# Top.net
KiCad netlist of a schematic drawn in Altium Designer
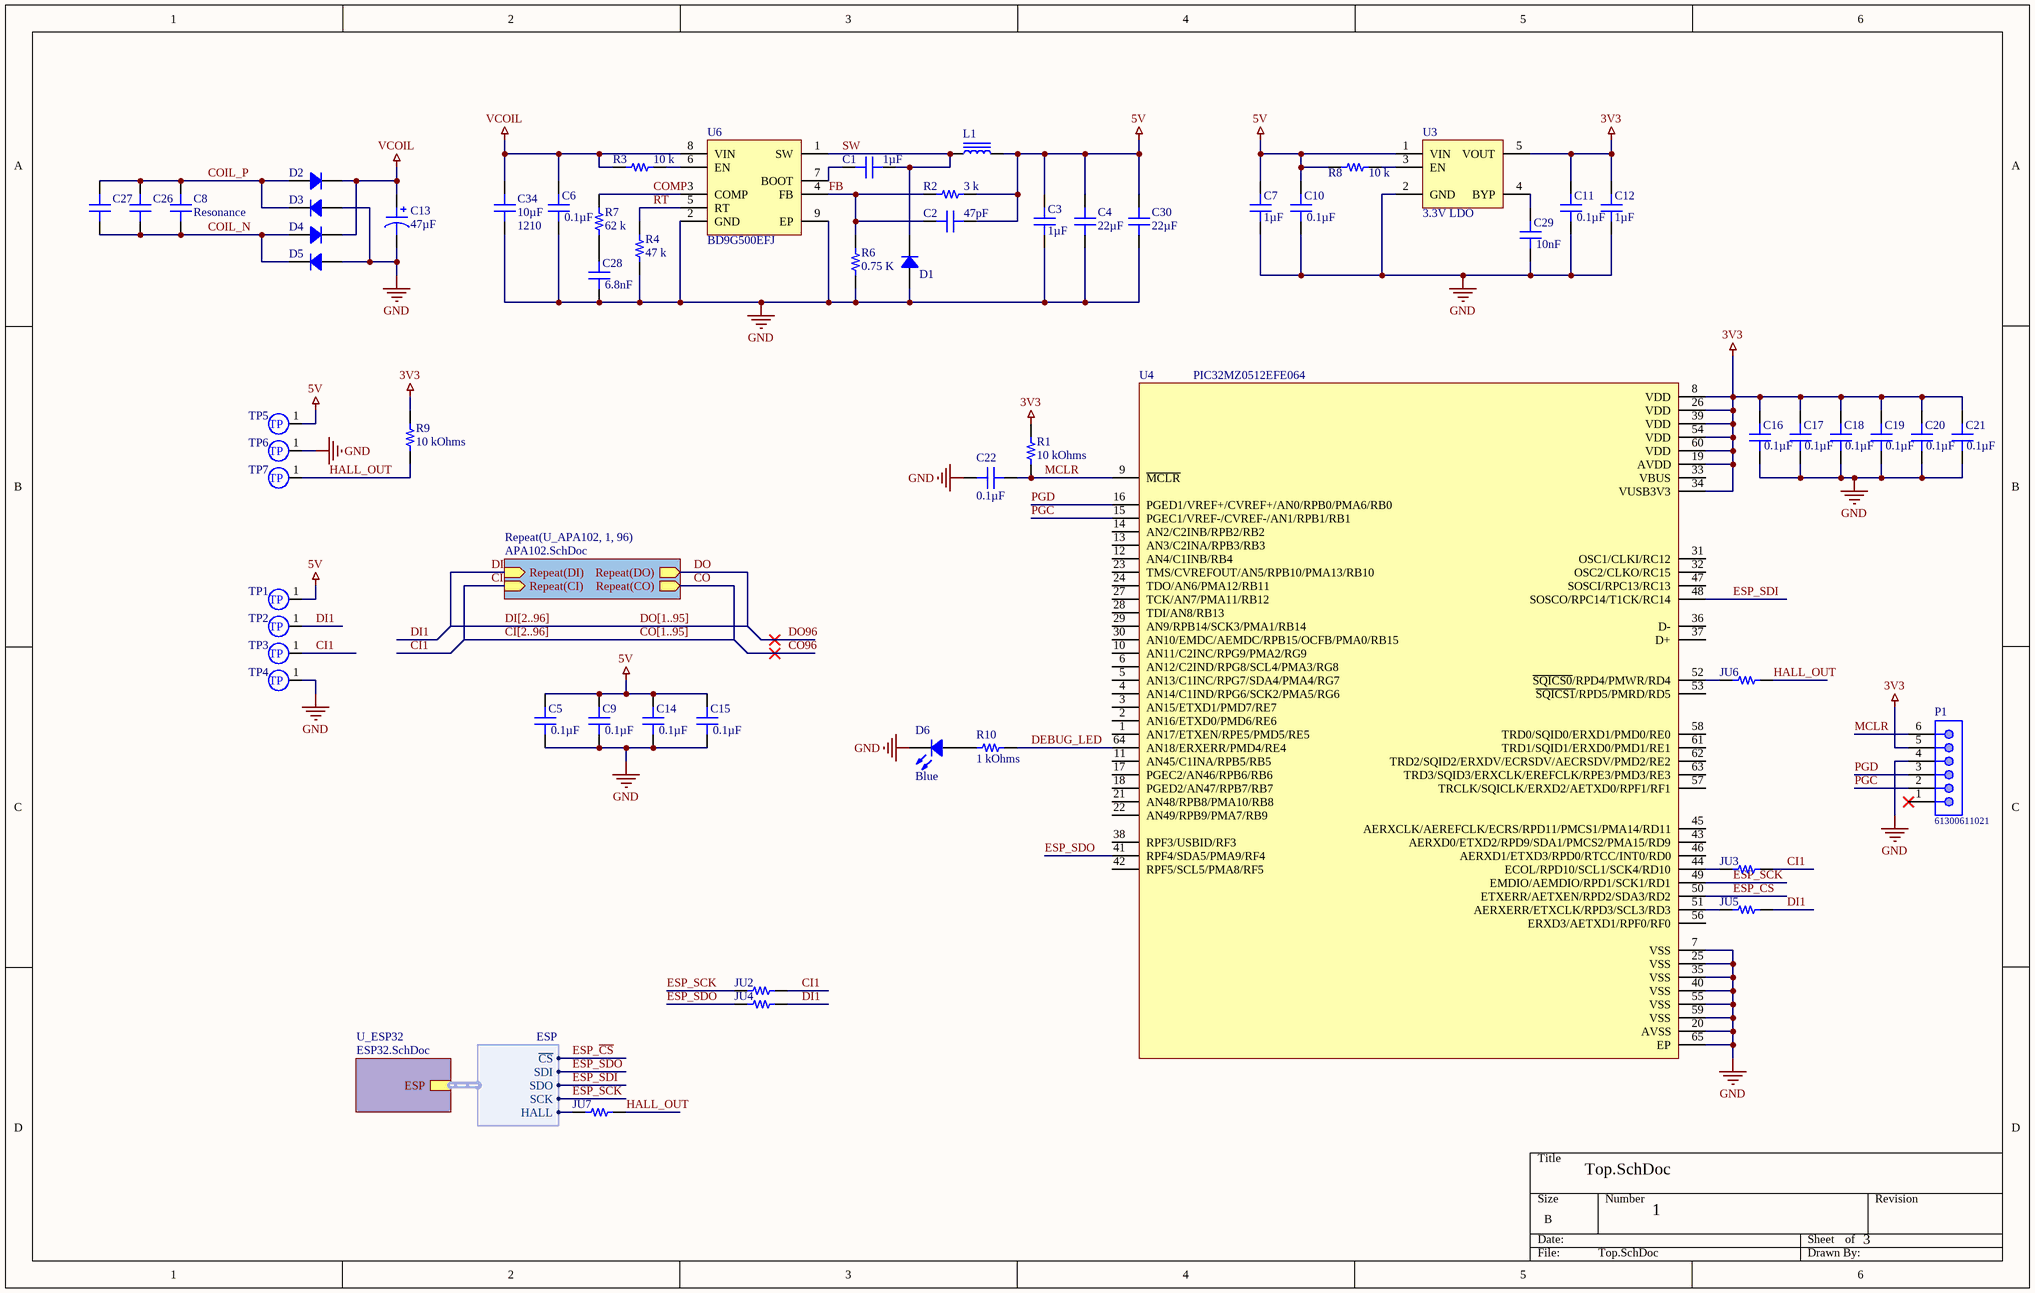
[diagram p0: Top.SchDoc]

(export (version "E")
  (design (tool "Eeschema 10.0.6"))
  (components
    (comp (ref "C1")
      (value "1µF")
      (footprint "CAP 0603_1608")
      (description "CAP CER 1UF 25V X7R 0603")
      (fields
        (field (name "PART NUMBER") "GCJ188R71E105KA01D")
        (field (name "MANUFACTURER") "Murata Electronics")
      )
      (libsource (lib "Celestial Altium Library - altium_library") (part "Capacitor"))
    )
    (comp (ref "C2")
      (value "47pF")
      (footprint "CAP 0603_1608")
      (description "CAP CER 47PF 100V NP0 0603")
      (fields
        (field (name "PART NUMBER") "C1608NP02A470J080AA")
        (field (name "MANUFACTURER") "TDK Corporation")
      )
      (libsource (lib "Celestial Altium Library - altium_library") (part "Capacitor"))
    )
    (comp (ref "C3")
      (value "1µF")
      (footprint "CAP 0603_1608")
      (description "CAP CER 1UF 25V X7R 0603")
      (fields
        (field (name "PART NUMBER") "GCJ188R71E105KA01D")
        (field (name "MANUFACTURER") "Murata Electronics")
      )
      (libsource (lib "Celestial Altium Library - altium_library") (part "Capacitor"))
    )
    (comp (ref "C4")
      (value "22µF")
      (footprint "CAP 0805_2012")
      (description "CAP CER 22UF 16V X5R 0805")
      (fields
        (field (name "PART NUMBER") "CL21A226MOQNNNE")
        (field (name "MANUFACTURER") "Samsung Electro-Mechanics")
      )
      (libsource (lib "Celestial Altium Library - altium_library") (part "Capacitor"))
    )
    (comp (ref "C5")
      (value "0.1µF")
      (footprint "CAP 0603_1608")
      (description "CAP CER 0.1UF 100V 0603 EPOXY")
      (fields
        (field (name "PART NUMBER") "GCG188R92A104KA03D")
        (field (name "MANUFACTURER") "Murata Electronics")
      )
      (libsource (lib "Celestial Altium Library - altium_library") (part "Capacitor"))
    )
    (comp (ref "C6")
      (value "0.1µF")
      (footprint "CAP 0603_1608")
      (description "CAP CER 0.1UF 100V 0603 EPOXY")
      (fields
        (field (name "PART NUMBER") "GCG188R92A104KA03D")
        (field (name "MANUFACTURER") "Murata Electronics")
      )
      (libsource (lib "Celestial Altium Library - altium_library") (part "Capacitor"))
    )
    (comp (ref "C7")
      (value "1µF")
      (footprint "CAP 0603_1608")
      (description "CAP CER 1UF 25V X7R 0603")
      (fields
        (field (name "PART NUMBER") "GCJ188R71E105KA01D")
        (field (name "MANUFACTURER") "Murata Electronics")
      )
      (libsource (lib "Celestial Altium Library - altium_library") (part "Capacitor"))
    )
    (comp (ref "C8")
      (value "Resonance")
      (footprint "CAP 1206_3216 - 1.8MM")
      (description "CAP, MLCC, 1206/3216, 100V, X7R,")
      (fields (field (name "PART NUMBER") "HMF316B7103KFHT") (field (name "MANUFACTURER") "Taiyo Yuden"))
      (libsource (lib "Celestial Altium Library - altium_library") (part "Capacitor"))
    )
    (comp (ref "C9")
      (value "0.1µF")
      (footprint "CAP 0603_1608")
      (description "CAP CER 0.1UF 100V 0603 EPOXY")
      (fields
        (field (name "PART NUMBER") "GCG188R92A104KA03D")
        (field (name "MANUFACTURER") "Murata Electronics")
      )
      (libsource (lib "Celestial Altium Library - altium_library") (part "Capacitor"))
    )
    (comp (ref "C10")
      (value "0.1µF")
      (footprint "CAP 0603_1608")
      (description "CAP CER 0.1UF 100V 0603 EPOXY")
      (fields
        (field (name "PART NUMBER") "GCG188R92A104KA03D")
        (field (name "MANUFACTURER") "Murata Electronics")
      )
      (libsource (lib "Celestial Altium Library - altium_library") (part "Capacitor"))
    )
    (comp (ref "C11")
      (value "0.1µF")
      (footprint "CAP 0603_1608")
      (description "CAP CER 0.1UF 100V 0603 EPOXY")
      (fields
        (field (name "PART NUMBER") "GCG188R92A104KA03D")
        (field (name "MANUFACTURER") "Murata Electronics")
      )
      (libsource (lib "Celestial Altium Library - altium_library") (part "Capacitor"))
    )
    (comp (ref "C12")
      (value "1µF")
      (footprint "CAP 0603_1608")
      (description "CAP CER 1UF 25V X7R 0603")
      (fields
        (field (name "PART NUMBER") "GCJ188R71E105KA01D")
        (field (name "MANUFACTURER") "Murata Electronics")
      )
      (libsource (lib "Celestial Altium Library - altium_library") (part "Capacitor"))
    )
    (comp (ref "C13")
      (value "47µF")
      (footprint "CAP ALSMD 6.6MM H6.1MM")
      (description "ALUMINUM CAPACITOR")
      (fields
        (field (name "PART NUMBER") "EMHL160ARA470MF61G")
        (field (name "MANUFACTURER") "United Chemi-Con")
      )
      (libsource (lib "Celestial Altium Library - altium_library") (part "Polarised Capacitor"))
    )
    (comp (ref "C14")
      (value "0.1µF")
      (footprint "CAP 0603_1608")
      (description "CAP CER 0.1UF 100V 0603 EPOXY")
      (fields
        (field (name "PART NUMBER") "GCG188R92A104KA03D")
        (field (name "MANUFACTURER") "Murata Electronics")
      )
      (libsource (lib "Celestial Altium Library - altium_library") (part "Capacitor"))
    )
    (comp (ref "C15")
      (value "0.1µF")
      (footprint "CAP 0603_1608")
      (description "CAP CER 0.1UF 100V 0603 EPOXY")
      (fields
        (field (name "PART NUMBER") "GCG188R92A104KA03D")
        (field (name "MANUFACTURER") "Murata Electronics")
      )
      (libsource (lib "Celestial Altium Library - altium_library") (part "Capacitor"))
    )
    (comp (ref "C16")
      (value "0.1µF")
      (footprint "CAP 0603_1608")
      (description "CAP CER 0.1UF 100V 0603 EPOXY")
      (fields
        (field (name "PART NUMBER") "GCG188R92A104KA03D")
        (field (name "MANUFACTURER") "Murata Electronics")
      )
      (libsource (lib "Celestial Altium Library - altium_library") (part "Capacitor"))
    )
    (comp (ref "C17")
      (value "0.1µF")
      (footprint "CAP 0603_1608")
      (description "CAP CER 0.1UF 100V 0603 EPOXY")
      (fields
        (field (name "PART NUMBER") "GCG188R92A104KA03D")
        (field (name "MANUFACTURER") "Murata Electronics")
      )
      (libsource (lib "Celestial Altium Library - altium_library") (part "Capacitor"))
    )
    (comp (ref "C18")
      (value "0.1µF")
      (footprint "CAP 0603_1608")
      (description "CAP CER 0.1UF 100V 0603 EPOXY")
      (fields
        (field (name "PART NUMBER") "GCG188R92A104KA03D")
        (field (name "MANUFACTURER") "Murata Electronics")
      )
      (libsource (lib "Celestial Altium Library - altium_library") (part "Capacitor"))
    )
    (comp (ref "C19")
      (value "0.1µF")
      (footprint "CAP 0603_1608")
      (description "CAP CER 0.1UF 100V 0603 EPOXY")
      (fields
        (field (name "PART NUMBER") "GCG188R92A104KA03D")
        (field (name "MANUFACTURER") "Murata Electronics")
      )
      (libsource (lib "Celestial Altium Library - altium_library") (part "Capacitor"))
    )
    (comp (ref "C20")
      (value "0.1µF")
      (footprint "CAP 0603_1608")
      (description "CAP CER 0.1UF 100V 0603 EPOXY")
      (fields
        (field (name "PART NUMBER") "GCG188R92A104KA03D")
        (field (name "MANUFACTURER") "Murata Electronics")
      )
      (libsource (lib "Celestial Altium Library - altium_library") (part "Capacitor"))
    )
    (comp (ref "C21")
      (value "0.1µF")
      (footprint "CAP 0603_1608")
      (description "CAP CER 0.1UF 100V 0603 EPOXY")
      (fields
        (field (name "PART NUMBER") "GCG188R92A104KA03D")
        (field (name "MANUFACTURER") "Murata Electronics")
      )
      (libsource (lib "Celestial Altium Library - altium_library") (part "Capacitor"))
    )
    (comp (ref "C22")
      (value "0.1µF")
      (footprint "CAP 0603_1608")
      (description "CAP CER 0.1UF 100V 0603 EPOXY")
      (fields
        (field (name "PART NUMBER") "GCG188R92A104KA03D")
        (field (name "MANUFACTURER") "Murata Electronics")
      )
      (libsource (lib "Celestial Altium Library - altium_library") (part "Capacitor"))
    )
    (comp (ref "C26")
      (value "Resonance")
      (footprint "CAP 1206_3216 - 1.8MM")
      (description "CAP, MLCC, 1206/3216, 100V, X7R,")
      (fields (field (name "PART NUMBER") "HMF316B7103KFHT") (field (name "MANUFACTURER") "Taiyo Yuden"))
      (libsource (lib "Celestial Altium Library - altium_library") (part "Capacitor"))
    )
    (comp (ref "C27")
      (value "Resonance")
      (footprint "CAP 1206_3216 - 1.8MM")
      (description "CAP, MLCC, 1206/3216, 100V, X7R,")
      (fields (field (name "PART NUMBER") "HMF316B7103KFHT") (field (name "MANUFACTURER") "Taiyo Yuden"))
      (libsource (lib "Celestial Altium Library - altium_library") (part "Capacitor"))
    )
    (comp (ref "C28")
      (value "6.8nF")
      (footprint "CAP 0603_1608")
      (description "CAP CER 0.1UF 100V 0603 EPOXY")
      (fields
        (field (name "PART NUMBER") "GCG188R92A104KA03D")
        (field (name "MANUFACTURER") "Murata Electronics")
      )
      (libsource (lib "Celestial Altium Library - altium_library") (part "Capacitor"))
    )
    (comp (ref "C29")
      (value "10nF")
      (footprint "CAP 0603_1608")
      (description "CAP CER 0.1UF 100V 0603 EPOXY")
      (fields
        (field (name "PART NUMBER") "GCG188R92A104KA03D")
        (field (name "MANUFACTURER") "Murata Electronics")
      )
      (libsource (lib "Celestial Altium Library - altium_library") (part "Capacitor"))
    )
    (comp (ref "C30")
      (value "22µF")
      (footprint "CAP 0805_2012")
      (description "CAP CER 22UF 16V X5R 0805")
      (fields
        (field (name "PART NUMBER") "CL21A226MOQNNNE")
        (field (name "MANUFACTURER") "Samsung Electro-Mechanics")
      )
      (libsource (lib "Celestial Altium Library - altium_library") (part "Capacitor"))
    )
    (comp (ref "C34")
      (value "10µF")
      (footprint "CAP 1210_3225 - 2.8MM")
      (description "CAP CER 100UF 16V X5R 1210")
      (fields
        (field (name "PART NUMBER") "EMK325ABJ107MM-P")
        (field (name "DEVICE PACKAGE") "1210")
        (field (name "MANUFACTURER") "Taiyo Yuden")
      )
      (libsource (lib "Celestial Altium Library - altium_library") (part "Capacitor"))
    )
    (comp (ref "D1")
      (value "STPS340UY")
      (footprint "DO214AA SMB")
      (description "DIODE SCHOTTKY 40V 3A SMB")
      (fields (field (name "MANUFACTURER") "STMicroelectronics"))
      (libsource (lib "Celestial Altium Library - altium_library") (part "Diode"))
    )
    (comp (ref "D2")
      (value "STPS340UY")
      (footprint "DO214AA SMB")
      (description "DIODE SCHOTTKY 40V 3A SMB")
      (fields (field (name "MANUFACTURER") "STMicroelectronics"))
      (libsource (lib "Celestial Altium Library - altium_library") (part "Diode"))
    )
    (comp (ref "D3")
      (value "STPS340UY")
      (footprint "DO214AA SMB")
      (description "DIODE SCHOTTKY 40V 3A SMB")
      (fields (field (name "MANUFACTURER") "STMicroelectronics"))
      (libsource (lib "Celestial Altium Library - altium_library") (part "Diode"))
    )
    (comp (ref "D4")
      (value "STPS340UY")
      (footprint "DO214AA SMB")
      (description "DIODE SCHOTTKY 40V 3A SMB")
      (fields (field (name "MANUFACTURER") "STMicroelectronics"))
      (libsource (lib "Celestial Altium Library - altium_library") (part "Diode"))
    )
    (comp (ref "D5")
      (value "STPS340UY")
      (footprint "DO214AA SMB")
      (description "DIODE SCHOTTKY 40V 3A SMB")
      (fields (field (name "MANUFACTURER") "STMicroelectronics"))
      (libsource (lib "Celestial Altium Library - altium_library") (part "Diode"))
    )
    (comp (ref "D6")
      (value "Blue")
      (footprint "LED 0603_1608 GREEN")
      (description "Blue LED")
      (fields (field (name "PART NUMBER") "XZCDGK53W-8VF") (field (name "MANUFACTURER") "SunLED"))
      (libsource (lib "Celestial Altium Library - altium_library") (part "LED"))
    )
    (comp (ref "JU2")
      (value "~")
      (footprint "RES 0805_2012")
      (description "Jumper")
      (fields
        (field (name "PART NUMBER") "TLRZ2ATTD")
        (field (name "MANUFACTURER") "KOA Speer Electronics, Inc.")
      )
      (libsource (lib "Celestial Altium Library - altium_library") (part "Resistor"))
    )
    (comp (ref "JU3")
      (value "~")
      (footprint "RES 0805_2012")
      (description "Jumper")
      (fields
        (field (name "PART NUMBER") "TLRZ2ATTD")
        (field (name "MANUFACTURER") "KOA Speer Electronics, Inc.")
      )
      (libsource (lib "Celestial Altium Library - altium_library") (part "Resistor"))
    )
    (comp (ref "JU4")
      (value "~")
      (footprint "RES 0805_2012")
      (description "Jumper")
      (fields
        (field (name "PART NUMBER") "TLRZ2ATTD")
        (field (name "MANUFACTURER") "KOA Speer Electronics, Inc.")
      )
      (libsource (lib "Celestial Altium Library - altium_library") (part "Resistor"))
    )
    (comp (ref "JU5")
      (value "~")
      (footprint "RES 0805_2012")
      (description "Jumper")
      (fields
        (field (name "PART NUMBER") "TLRZ2ATTD")
        (field (name "MANUFACTURER") "KOA Speer Electronics, Inc.")
      )
      (libsource (lib "Celestial Altium Library - altium_library") (part "Resistor"))
    )
    (comp (ref "JU6")
      (value "~")
      (footprint "RES 0805_2012")
      (description "Jumper")
      (fields
        (field (name "PART NUMBER") "TLRZ2ATTD")
        (field (name "MANUFACTURER") "KOA Speer Electronics, Inc.")
      )
      (libsource (lib "Celestial Altium Library - altium_library") (part "Resistor"))
    )
    (comp (ref "JU7")
      (value "~")
      (footprint "RES 0805_2012")
      (description "Jumper")
      (fields
        (field (name "PART NUMBER") "TLRZ2ATTD")
        (field (name "MANUFACTURER") "KOA Speer Electronics, Inc.")
      )
      (libsource (lib "Celestial Altium Library - altium_library") (part "Resistor"))
    )
    (comp (ref "L1")
      (value "MPL-AL5050-5R6")
      (footprint "MPL-AL5050-5R6")
      (description "FIXED IND 5.6UH 6.8A 20 MOHM SMD")
      (fields (field (name "MF") "Laird-Signal Integrity Products") (field (name "MP") "MGV05021R0M-10"))
      (libsource (lib "IC") (part "MPL-AL5050-5R6"))
    )
    (comp (ref "P1")
      (value "61300611021")
      (footprint "61300611021")
      (description "WR-PHD Pin Header, THT, pitch 2.54mm, Single Row, Angled, 6p")
      (fields (field (name "MANUFACTURER") "Wurth Elektronik"))
      (libsource (lib "IC") (part "6pin right angle header - no holes"))
    )
    (comp (ref "R1")
      (value "10 kOhms")
      (footprint "RES 0603_1608")
      (description "RES 10K OHM 0.1% 1/16W 0603")
      (fields
        (field (name "PART NUMBER") "RNCS0603BKE10K0")
        (field (name "MANUFACTURER") "Stackpole Electronics Inc")
      )
      (libsource (lib "Celestial Altium Library - altium_library") (part "Resistor"))
    )
    (comp (ref "R2")
      (value "3 k")
      (footprint "RES 0603_1608")
      (description "RES SMD 40.2KOHM 0.5% 1/10W 0603")
      (fields (field (name "PART NUMBER") "RT0603DRD0740K2L") (field (name "MANUFACTURER") "Yageo"))
      (libsource (lib "Celestial Altium Library - altium_library") (part "Resistor"))
    )
    (comp (ref "R3")
      (value "10 k")
      (footprint "RES 0603_1608")
      (description "RES 10K OHM 0.1% 1/16W 0603")
      (fields
        (field (name "PART NUMBER") "RNCS0603BKE10K0")
        (field (name "MANUFACTURER") "Stackpole Electronics Inc")
      )
      (libsource (lib "Celestial Altium Library - altium_library") (part "Resistor"))
    )
    (comp (ref "R4")
      (value "47 k")
      (footprint "RES 0603_1608")
      (description "RES 10K OHM 0.1% 1/16W 0603")
      (fields
        (field (name "PART NUMBER") "RNCS0603BKE10K0")
        (field (name "MANUFACTURER") "Stackpole Electronics Inc")
      )
      (libsource (lib "Celestial Altium Library - altium_library") (part "Resistor"))
    )
    (comp (ref "R6")
      (value "0.75 K")
      (footprint "RES 0603_1608")
      (description "RES 7.68K OHM 1% 1/10W 0603")
      (fields
        (field (name "PART NUMBER") "RMCF0603FT7K68")
        (field (name "MANUFACTURER") "Stackpole Electronics Inc")
      )
      (libsource (lib "Celestial Altium Library - altium_library") (part "Resistor"))
    )
    (comp (ref "R7")
      (value "62 k")
      (footprint "RES 0603_1608")
      (description "RES 10K OHM 0.1% 1/16W 0603")
      (fields
        (field (name "PART NUMBER") "RNCS0603BKE10K0")
        (field (name "MANUFACTURER") "Stackpole Electronics Inc")
      )
      (libsource (lib "Celestial Altium Library - altium_library") (part "Resistor"))
    )
    (comp (ref "R8")
      (value "10 k")
      (footprint "RES 0603_1608")
      (description "RES 10K OHM 0.1% 1/16W 0603")
      (fields
        (field (name "PART NUMBER") "RNCS0603BKE10K0")
        (field (name "MANUFACTURER") "Stackpole Electronics Inc")
      )
      (libsource (lib "Celestial Altium Library - altium_library") (part "Resistor"))
    )
    (comp (ref "R9")
      (value "10 kOhms")
      (footprint "RES 0603_1608")
      (description "RES 10K OHM 0.1% 1/16W 0603")
      (fields
        (field (name "PART NUMBER") "RNCS0603BKE10K0")
        (field (name "MANUFACTURER") "Stackpole Electronics Inc")
      )
      (libsource (lib "Celestial Altium Library - altium_library") (part "Resistor"))
    )
    (comp (ref "R10")
      (value "1 kOhms")
      (footprint "RES 0603_1608")
      (description "RES 1K OHM 0.5% 1/10W 0603")
      (fields
        (field (name "PART NUMBER") "RNCF0603DTE1K00")
        (field (name "MANUFACTURER") "Stackpole Electronics Inc")
      )
      (libsource (lib "Celestial Altium Library - altium_library") (part "Resistor"))
    )
    (comp (ref "TP1")
      (value "TP")
      (footprint "TP")
      (description "Test point")
      (libsource (lib "IC") (part "TP"))
    )
    (comp (ref "TP2")
      (value "TP")
      (footprint "TP")
      (description "Test point")
      (libsource (lib "IC") (part "TP"))
    )
    (comp (ref "TP3")
      (value "TP")
      (footprint "TP")
      (description "Test point")
      (libsource (lib "IC") (part "TP"))
    )
    (comp (ref "TP4")
      (value "TP")
      (footprint "TP")
      (description "Test point")
      (libsource (lib "IC") (part "TP"))
    )
    (comp (ref "TP5")
      (value "TP")
      (footprint "TP")
      (description "Test point")
      (libsource (lib "IC") (part "TP"))
    )
    (comp (ref "TP6")
      (value "TP")
      (footprint "TP")
      (description "Test point")
      (libsource (lib "IC") (part "TP"))
    )
    (comp (ref "TP7")
      (value "TP")
      (footprint "TP")
      (description "Test point")
      (libsource (lib "IC") (part "TP"))
    )
    (comp (ref "U3")
      (value "3.3V LDO")
      (footprint "TI SOT-23-5 DBV")
      (libsource (lib "IC") (part "MIC5504-3.3YM5"))
    )
    (comp (ref "U4")
      (value "PIC32MZ0512EFE064")
      (footprint "QFN50P900X900X100-65N")
      (description "32-bit Microcontrollers - MCU 32-BIT MCU 512KB FL 128KB RAM, No Crypto")
      (fields (field (name "MF") "Microchip") (field (name "MP") "PIC32MZ2048EFG064T-I/PT"))
      (libsource (lib "IC") (part "PIC32MZ0512EFE064-I/PT"))
    )
    (comp (ref "U6")
      (value "BD9G500EFJ")
      (footprint "SOP127P600X100-9N")
      (description "5A Buck")
      (libsource (lib "IC") (part "BD9G500EFJ"))
    )
  )
  (nets
    (net (code "193") (name "/CI1") (class "Default")
      (node (ref "JU2") (pin "1") (pinfunction "1_1") (pintype "passive"))
      (node (ref "JU3") (pin "1") (pinfunction "1_1") (pintype "passive"))
      (node (ref "TP3") (pin "1") (pinfunction "TP_1") (pintype "passive"))
    )
    (net (code "197") (name "/COIL_N") (class "Default")
      (node (ref "C26") (pin "1") (pinfunction "1_1") (pintype "passive"))
      (node (ref "C27") (pin "1") (pinfunction "1_1") (pintype "passive"))
      (node (ref "C8") (pin "1") (pinfunction "1_1") (pintype "passive"))
      (node (ref "D4") (pin "1") (pinfunction "1_1") (pintype "passive"))
      (node (ref "D5") (pin "2") (pinfunction "2_2") (pintype "passive"))
    )
    (net (code "198") (name "/COIL_P") (class "Default")
      (node (ref "C26") (pin "2") (pinfunction "2_2") (pintype "passive"))
      (node (ref "C27") (pin "2") (pinfunction "2_2") (pintype "passive"))
      (node (ref "C8") (pin "2") (pinfunction "2_2") (pintype "passive"))
      (node (ref "D2") (pin "1") (pinfunction "1_1") (pintype "passive"))
      (node (ref "D3") (pin "2") (pinfunction "2_2") (pintype "passive"))
    )
    (net (code "199") (name "/COMP") (class "Default")
      (node (ref "R7") (pin "1") (pinfunction "1_1") (pintype "passive"))
      (node (ref "U6") (pin "3") (pinfunction "COMP_3") (pintype "passive"))
    )
    (net (code "200") (name "/DEBUG_LED") (class "Default")
      (node (ref "R10") (pin "1") (pinfunction "1_1") (pintype "passive"))
      (node (ref "U4") (pin "64") (pinfunction "AN18/ERXERR/PMD4/RE4_64") (pintype "passive"))
    )
    (net (code "202") (name "/DI1") (class "Default")
      (node (ref "JU4") (pin "1") (pinfunction "1_1") (pintype "passive"))
      (node (ref "JU5") (pin "1") (pinfunction "1_1") (pintype "passive"))
      (node (ref "TP2") (pin "1") (pinfunction "TP_1") (pintype "passive"))
    )
    (net (code "206") (name "/ESP_SCK") (class "Default")
      (node (ref "JU2") (pin "2") (pinfunction "2_2") (pintype "passive"))
      (node (ref "U4") (pin "49") (pinfunction "EMDIO/AEMDIO/RPD1/SCK1/RD1_49") (pintype "passive"))
    )
    (net (code "207") (name "/ESP_SDI") (class "Default")
      (node (ref "U4") (pin "48") (pinfunction "SOSCO/RPC14/T1CK/RC14_48") (pintype "passive"))
    )
    (net (code "208") (name "/ESP_SDO") (class "Default")
      (node (ref "JU4") (pin "2") (pinfunction "2_2") (pintype "passive"))
      (node (ref "U4") (pin "41") (pinfunction "RPF4/SDA5/PMA9/RF4_41") (pintype "passive"))
    )
    (net (code "209") (name "/ESP_~{CS}") (class "Default")
      (node (ref "U4") (pin "50") (pinfunction "ETXERR/AETXEN/RPD2/SDA3/RD2_50") (pintype "passive"))
    )
    (net (code "210") (name "/FB") (class "Default")
      (node (ref "C2") (pin "2") (pinfunction "2_2") (pintype "passive"))
      (node (ref "R2") (pin "1") (pinfunction "1_1") (pintype "passive"))
      (node (ref "R6") (pin "2") (pinfunction "2_2") (pintype "passive"))
      (node (ref "U6") (pin "4") (pinfunction "FB_4") (pintype "passive"))
    )
    (net (code "211") (name "/HALL") (class "Default")
      (node (ref "JU7") (pin "2") (pinfunction "2_2") (pintype "passive"))
    )
    (net (code "212") (name "/HALL_OUT") (class "Default")
      (node (ref "JU6") (pin "1") (pinfunction "1_1") (pintype "passive"))
      (node (ref "JU7") (pin "1") (pinfunction "1_1") (pintype "passive"))
      (node (ref "R9") (pin "1") (pinfunction "1_1") (pintype "passive"))
      (node (ref "TP7") (pin "1") (pinfunction "TP_1") (pintype "passive"))
    )
    (net (code "213") (name "/MCLR") (class "Default")
      (node (ref "C22") (pin "1") (pinfunction "1_1") (pintype "passive"))
      (node (ref "P1") (pin "6") (pinfunction "6_6") (pintype "passive"))
      (node (ref "R1") (pin "1") (pinfunction "1_1") (pintype "passive"))
      (node (ref "U4") (pin "9") (pinfunction "~{MCLR}_9") (pintype "passive"))
    )
    (net (code "214") (name "/PGC") (class "Default")
      (node (ref "P1") (pin "2") (pinfunction "2_2") (pintype "passive"))
      (node (ref "U4") (pin "15") (pinfunction "PGEC1/VREF-/CVREF-/AN1/RPB1/RB1_15") (pintype "passive"))
    )
    (net (code "215") (name "/PGD") (class "Default")
      (node (ref "P1") (pin "3") (pinfunction "3_3") (pintype "passive"))
      (node (ref "U4") (pin "16") (pinfunction "PGED1/VREF+/CVREF+/AN0/RPB0/PMA6/RB0_16") (pintype "passive"))
    )
    (net (code "216") (name "/RT") (class "Default")
      (node (ref "R4") (pin "1") (pinfunction "1_1") (pintype "passive"))
      (node (ref "U6") (pin "5") (pinfunction "RT_5") (pintype "passive"))
    )
    (net (code "217") (name "/SW") (class "Default")
      (node (ref "C1") (pin "2") (pinfunction "2_2") (pintype "passive"))
      (node (ref "D1") (pin "2") (pinfunction "2_2") (pintype "passive"))
      (node (ref "L1") (pin "1") (pinfunction "1_1") (pintype "passive"))
      (node (ref "U6") (pin "1") (pinfunction "SW_1") (pintype "passive"))
    )
    (net (code "219") (name "3V3") (class "Default")
      (node (ref "C11") (pin "1") (pinfunction "1_1") (pintype "passive"))
      (node (ref "C12") (pin "2") (pinfunction "2_2") (pintype "passive"))
      (node (ref "C16") (pin "1") (pinfunction "1_1") (pintype "passive"))
      (node (ref "C17") (pin "1") (pinfunction "1_1") (pintype "passive"))
      (node (ref "C18") (pin "1") (pinfunction "1_1") (pintype "passive"))
      (node (ref "C19") (pin "1") (pinfunction "1_1") (pintype "passive"))
      (node (ref "C20") (pin "1") (pinfunction "1_1") (pintype "passive"))
      (node (ref "C21") (pin "1") (pinfunction "1_1") (pintype "passive"))
      (node (ref "P1") (pin "5") (pinfunction "5_5") (pintype "passive"))
      (node (ref "R1") (pin "2") (pinfunction "2_2") (pintype "passive"))
      (node (ref "R9") (pin "2") (pinfunction "2_2") (pintype "passive"))
      (node (ref "U3") (pin "5") (pinfunction "VOUT_5") (pintype "passive"))
      (node (ref "U4") (pin "19") (pinfunction "AVDD_19") (pintype "power_in"))
      (node (ref "U4") (pin "26") (pinfunction "VDD_26") (pintype "power_in"))
      (node (ref "U4") (pin "34") (pinfunction "VUSB3V3_34") (pintype "power_in"))
      (node (ref "U4") (pin "39") (pinfunction "VDD_39") (pintype "power_in"))
      (node (ref "U4") (pin "54") (pinfunction "VDD_54") (pintype "power_in"))
      (node (ref "U4") (pin "60") (pinfunction "VDD_60") (pintype "power_in"))
      (node (ref "U4") (pin "8") (pinfunction "VDD_8") (pintype "power_in"))
    )
    (net (code "220") (name "5V") (class "Default")
      (node (ref "C10") (pin "1") (pinfunction "1_1") (pintype "passive"))
      (node (ref "C14") (pin "1") (pinfunction "1_1") (pintype "passive"))
      (node (ref "C15") (pin "1") (pinfunction "1_1") (pintype "passive"))
      (node (ref "C2") (pin "1") (pinfunction "1_1") (pintype "passive"))
      (node (ref "C3") (pin "2") (pinfunction "2_2") (pintype "passive"))
      (node (ref "C30") (pin "2") (pinfunction "2_2") (pintype "passive"))
      (node (ref "C4") (pin "2") (pinfunction "2_2") (pintype "passive"))
      (node (ref "C5") (pin "1") (pinfunction "1_1") (pintype "passive"))
      (node (ref "C7") (pin "2") (pinfunction "2_2") (pintype "passive"))
      (node (ref "C9") (pin "1") (pinfunction "1_1") (pintype "passive"))
      (node (ref "L1") (pin "2") (pinfunction "2_2") (pintype "passive"))
      (node (ref "R2") (pin "2") (pinfunction "2_2") (pintype "passive"))
      (node (ref "R8") (pin "2") (pinfunction "2_2") (pintype "passive"))
      (node (ref "TP1") (pin "1") (pinfunction "TP_1") (pintype "passive"))
      (node (ref "TP5") (pin "1") (pinfunction "TP_1") (pintype "passive"))
      (node (ref "U3") (pin "1") (pinfunction "VIN_1") (pintype "passive"))
    )
    (net (code "221") (name "GND") (class "Default")
      (node (ref "C10") (pin "2") (pinfunction "2_2") (pintype "passive"))
      (node (ref "C11") (pin "2") (pinfunction "2_2") (pintype "passive"))
      (node (ref "C12") (pin "1") (pinfunction "1_1") (pintype "passive"))
      (node (ref "C13") (pin "2") (pinfunction "2_2") (pintype "passive"))
      (node (ref "C14") (pin "2") (pinfunction "2_2") (pintype "passive"))
      (node (ref "C15") (pin "2") (pinfunction "2_2") (pintype "passive"))
      (node (ref "C16") (pin "2") (pinfunction "2_2") (pintype "passive"))
      (node (ref "C17") (pin "2") (pinfunction "2_2") (pintype "passive"))
      (node (ref "C18") (pin "2") (pinfunction "2_2") (pintype "passive"))
      (node (ref "C19") (pin "2") (pinfunction "2_2") (pintype "passive"))
      (node (ref "C20") (pin "2") (pinfunction "2_2") (pintype "passive"))
      (node (ref "C21") (pin "2") (pinfunction "2_2") (pintype "passive"))
      (node (ref "C22") (pin "2") (pinfunction "2_2") (pintype "passive"))
      (node (ref "C28") (pin "2") (pinfunction "2_2") (pintype "passive"))
      (node (ref "C29") (pin "2") (pinfunction "2_2") (pintype "passive"))
      (node (ref "C3") (pin "1") (pinfunction "1_1") (pintype "passive"))
      (node (ref "C30") (pin "1") (pinfunction "1_1") (pintype "passive"))
      (node (ref "C34") (pin "2") (pinfunction "2_2") (pintype "passive"))
      (node (ref "C4") (pin "1") (pinfunction "1_1") (pintype "passive"))
      (node (ref "C5") (pin "2") (pinfunction "2_2") (pintype "passive"))
      (node (ref "C6") (pin "2") (pinfunction "2_2") (pintype "passive"))
      (node (ref "C7") (pin "1") (pinfunction "1_1") (pintype "passive"))
      (node (ref "C9") (pin "2") (pinfunction "2_2") (pintype "passive"))
      (node (ref "D1") (pin "1") (pinfunction "1_1") (pintype "passive"))
      (node (ref "D3") (pin "1") (pinfunction "1_1") (pintype "passive"))
      (node (ref "D5") (pin "1") (pinfunction "1_1") (pintype "passive"))
      (node (ref "D6") (pin "2") (pinfunction "2_2") (pintype "passive"))
      (node (ref "P1") (pin "4") (pinfunction "4_4") (pintype "passive"))
      (node (ref "R4") (pin "2") (pinfunction "2_2") (pintype "passive"))
      (node (ref "R6") (pin "1") (pinfunction "1_1") (pintype "passive"))
      (node (ref "TP4") (pin "1") (pinfunction "TP_1") (pintype "passive"))
      (node (ref "TP6") (pin "1") (pinfunction "TP_1") (pintype "passive"))
      (node (ref "U3") (pin "2") (pinfunction "GND_2") (pintype "passive"))
      (node (ref "U4") (pin "20") (pinfunction "AVSS_20") (pintype "power_in"))
      (node (ref "U4") (pin "25") (pinfunction "VSS_25") (pintype "power_in"))
      (node (ref "U4") (pin "35") (pinfunction "VSS_35") (pintype "power_in"))
      (node (ref "U4") (pin "40") (pinfunction "VSS_40") (pintype "power_in"))
      (node (ref "U4") (pin "55") (pinfunction "VSS_55") (pintype "power_in"))
      (node (ref "U4") (pin "59") (pinfunction "VSS_59") (pintype "power_in"))
      (node (ref "U4") (pin "65") (pinfunction "EP_65") (pintype "power_in"))
      (node (ref "U4") (pin "7") (pinfunction "VSS_7") (pintype "power_in"))
      (node (ref "U6") (pin "2") (pinfunction "GND_2") (pintype "passive"))
      (node (ref "U6") (pin "9") (pinfunction "EP_9") (pintype "passive"))
    )
    (net (code "222") (name "Net-(C28-Pad1)") (class "Default")
      (node (ref "C28") (pin "1") (pinfunction "1_1") (pintype "passive"))
      (node (ref "R7") (pin "2") (pinfunction "2_2") (pintype "passive"))
    )
    (net (code "223") (name "Net-(D6-Pad1)") (class "Default")
      (node (ref "D6") (pin "1") (pinfunction "1_1") (pintype "passive"))
      (node (ref "R10") (pin "2") (pinfunction "2_2") (pintype "passive"))
    )
    (net (code "224") (name "Net-(U3-BYP)") (class "Default")
      (node (ref "C29") (pin "1") (pinfunction "1_1") (pintype "passive"))
      (node (ref "U3") (pin "4") (pinfunction "BYP_4") (pintype "passive"))
    )
    (net (code "225") (name "Net-(U3-EN)") (class "Default")
      (node (ref "R8") (pin "1") (pinfunction "1_1") (pintype "passive"))
      (node (ref "U3") (pin "3") (pinfunction "EN_3") (pintype "passive"))
    )
    (net (code "226") (name "Net-(U4-AERXERR{slash}ETXCLK{slash}RPD3{slash}SCL3{slash}RD3)") (class "Default")
      (node (ref "JU5") (pin "2") (pinfunction "2_2") (pintype "passive"))
      (node (ref "U4") (pin "51") (pinfunction "AERXERR/ETXCLK/RPD3/SCL3/RD3_51") (pintype "passive"))
    )
    (net (code "227") (name "Net-(U4-ECOL{slash}RPD10{slash}SCL1{slash}SCK4{slash}RD10)") (class "Default")
      (node (ref "JU3") (pin "2") (pinfunction "2_2") (pintype "passive"))
      (node (ref "U4") (pin "44") (pinfunction "ECOL/RPD10/SCL1/SCK4/RD10_44") (pintype "passive"))
    )
    (net (code "228") (name "Net-(U4-~{SQICS0}{slash}RPD4{slash}PMWR{slash}RD4)") (class "Default")
      (node (ref "JU6") (pin "2") (pinfunction "2_2") (pintype "passive"))
      (node (ref "U4") (pin "52") (pinfunction "~{SQICS0}/RPD4/PMWR/RD4_52") (pintype "passive"))
    )
    (net (code "229") (name "Net-(U6-BOOT)") (class "Default")
      (node (ref "C1") (pin "1") (pinfunction "1_1") (pintype "passive"))
      (node (ref "U6") (pin "7") (pinfunction "BOOT_7") (pintype "passive"))
    )
    (net (code "230") (name "Net-(U6-EN)") (class "Default")
      (node (ref "R3") (pin "1") (pinfunction "1_1") (pintype "passive"))
      (node (ref "U6") (pin "6") (pinfunction "EN_6") (pintype "passive"))
    )
    (net (code "231") (name "VCOIL") (class "Default")
      (node (ref "C13") (pin "1") (pinfunction "1_1") (pintype "passive"))
      (node (ref "C34") (pin "1") (pinfunction "1_1") (pintype "passive"))
      (node (ref "C6") (pin "1") (pinfunction "1_1") (pintype "passive"))
      (node (ref "D2") (pin "2") (pinfunction "2_2") (pintype "passive"))
      (node (ref "D4") (pin "2") (pinfunction "2_2") (pintype "passive"))
      (node (ref "R3") (pin "2") (pinfunction "2_2") (pintype "passive"))
      (node (ref "U6") (pin "8") (pinfunction "VIN_8") (pintype "passive"))
    )
    (net (code "232") (name "unconnected-(P1-Pad1)") (class "Default")
      (node (ref "P1") (pin "1") (pinfunction "1_1") (pintype "passive+no_connect"))
    )
    (net (code "233") (name "unconnected-(U4-AERXCLK{slash}AEREFCLK{slash}ECRS{slash}RPD11{slash}PMCS1{slash}PMA14{slash}RD11-Pad45)") (class "Default")
      (node (ref "U4") (pin "45") (pinfunction "AERXCLK/AEREFCLK/ECRS/RPD11/PMCS1/PMA14/RD11_45") (pintype "passive"))
    )
    (net (code "234") (name "unconnected-(U4-AERXD0{slash}ETXD2{slash}RPD9{slash}SDA1{slash}PMCS2{slash}PMA15{slash}RD9-Pad43)") (class "Default")
      (node (ref "U4") (pin "43") (pinfunction "AERXD0/ETXD2/RPD9/SDA1/PMCS2/PMA15/RD9_43") (pintype "passive"))
    )
    (net (code "235") (name "unconnected-(U4-AERXD1{slash}ETXD3{slash}RPD0{slash}RTCC{slash}INT0{slash}RD0-Pad46)") (class "Default")
      (node (ref "U4") (pin "46") (pinfunction "AERXD1/ETXD3/RPD0/RTCC/INT0/RD0_46") (pintype "passive"))
    )
    (net (code "236") (name "unconnected-(U4-AN2{slash}C2INB{slash}RPB2{slash}RB2-Pad14)") (class "Default")
      (node (ref "U4") (pin "14") (pinfunction "AN2/C2INB/RPB2/RB2_14") (pintype "passive"))
    )
    (net (code "237") (name "unconnected-(U4-AN3{slash}C2INA{slash}RPB3{slash}RB3-Pad13)") (class "Default")
      (node (ref "U4") (pin "13") (pinfunction "AN3/C2INA/RPB3/RB3_13") (pintype "passive"))
    )
    (net (code "238") (name "unconnected-(U4-AN4{slash}C1INB{slash}RB4-Pad12)") (class "Default")
      (node (ref "U4") (pin "12") (pinfunction "AN4/C1INB/RB4_12") (pintype "passive"))
    )
    (net (code "239") (name "unconnected-(U4-AN9{slash}RPB14{slash}SCK3{slash}PMA1{slash}RB14-Pad29)") (class "Default")
      (node (ref "U4") (pin "29") (pinfunction "AN9/RPB14/SCK3/PMA1/RB14_29") (pintype "passive"))
    )
    (net (code "240") (name "unconnected-(U4-AN10{slash}EMDC{slash}AEMDC{slash}RPB15{slash}OCFB{slash}PMA0{slash}RB15-Pad30)") (class "Default")
      (node (ref "U4") (pin "30") (pinfunction "AN10/EMDC/AEMDC/RPB15/OCFB/PMA0/RB15_30") (pintype "passive"))
    )
    (net (code "241") (name "unconnected-(U4-AN11{slash}C2INC{slash}RPG9{slash}PMA2{slash}RG9-Pad10)") (class "Default")
      (node (ref "U4") (pin "10") (pinfunction "AN11/C2INC/RPG9/PMA2/RG9_10") (pintype "passive"))
    )
    (net (code "242") (name "unconnected-(U4-AN12{slash}C2IND{slash}RPG8{slash}SCL4{slash}PMA3{slash}RG8-Pad6)") (class "Default")
      (node (ref "U4") (pin "6") (pinfunction "AN12/C2IND/RPG8/SCL4/PMA3/RG8_6") (pintype "passive"))
    )
    (net (code "243") (name "unconnected-(U4-AN13{slash}C1INC{slash}RPG7{slash}SDA4{slash}PMA4{slash}RG7-Pad5)") (class "Default")
      (node (ref "U4") (pin "5") (pinfunction "AN13/C1INC/RPG7/SDA4/PMA4/RG7_5") (pintype "passive"))
    )
    (net (code "244") (name "unconnected-(U4-AN14{slash}C1IND{slash}RPG6{slash}SCK2{slash}PMA5{slash}RG6-Pad4)") (class "Default")
      (node (ref "U4") (pin "4") (pinfunction "AN14/C1IND/RPG6/SCK2/PMA5/RG6_4") (pintype "passive"))
    )
    (net (code "245") (name "unconnected-(U4-AN15{slash}ETXD1{slash}PMD7{slash}RE7-Pad3)") (class "Default")
      (node (ref "U4") (pin "3") (pinfunction "AN15/ETXD1/PMD7/RE7_3") (pintype "passive"))
    )
    (net (code "246") (name "unconnected-(U4-AN16{slash}ETXD0{slash}PMD6{slash}RE6-Pad2)") (class "Default")
      (node (ref "U4") (pin "2") (pinfunction "AN16/ETXD0/PMD6/RE6_2") (pintype "passive"))
    )
    (net (code "247") (name "unconnected-(U4-AN17{slash}ETXEN{slash}RPE5{slash}PMD5{slash}RE5-Pad1)") (class "Default")
      (node (ref "U4") (pin "1") (pinfunction "AN17/ETXEN/RPE5/PMD5/RE5_1") (pintype "passive"))
    )
    (net (code "248") (name "unconnected-(U4-AN45{slash}C1INA{slash}RPB5{slash}RB5-Pad11)") (class "Default")
      (node (ref "U4") (pin "11") (pinfunction "AN45/C1INA/RPB5/RB5_11") (pintype "passive"))
    )
    (net (code "249") (name "unconnected-(U4-AN48{slash}RPB8{slash}PMA10{slash}RB8-Pad21)") (class "Default")
      (node (ref "U4") (pin "21") (pinfunction "AN48/RPB8/PMA10/RB8_21") (pintype "passive"))
    )
    (net (code "250") (name "unconnected-(U4-AN49{slash}RPB9{slash}PMA7{slash}RB9-Pad22)") (class "Default")
      (node (ref "U4") (pin "22") (pinfunction "AN49/RPB9/PMA7/RB9_22") (pintype "passive"))
    )
    (net (code "251") (name "unconnected-(U4-D+-Pad37)") (class "Default")
      (node (ref "U4") (pin "37") (pinfunction "D+_37") (pintype "passive"))
    )
    (net (code "252") (name "unconnected-(U4-D--Pad36)") (class "Default")
      (node (ref "U4") (pin "36") (pinfunction "D-_36") (pintype "passive"))
    )
    (net (code "253") (name "unconnected-(U4-ERXD3{slash}AETXD1{slash}RPF0{slash}RF0-Pad56)") (class "Default")
      (node (ref "U4") (pin "56") (pinfunction "ERXD3/AETXD1/RPF0/RF0_56") (pintype "passive"))
    )
    (net (code "254") (name "unconnected-(U4-OSC1{slash}CLKI{slash}RC12-Pad31)") (class "Default")
      (node (ref "U4") (pin "31") (pinfunction "OSC1/CLKI/RC12_31") (pintype "passive"))
    )
    (net (code "255") (name "unconnected-(U4-OSC2{slash}CLKO{slash}RC15-Pad32)") (class "Default")
      (node (ref "U4") (pin "32") (pinfunction "OSC2/CLKO/RC15_32") (pintype "passive"))
    )
    (net (code "256") (name "unconnected-(U4-PGEC2{slash}AN46{slash}RPB6{slash}RB6-Pad17)") (class "Default")
      (node (ref "U4") (pin "17") (pinfunction "PGEC2/AN46/RPB6/RB6_17") (pintype "passive"))
    )
    (net (code "257") (name "unconnected-(U4-PGED2{slash}AN47{slash}RPB7{slash}RB7-Pad18)") (class "Default")
      (node (ref "U4") (pin "18") (pinfunction "PGED2/AN47/RPB7/RB7_18") (pintype "passive"))
    )
    (net (code "258") (name "unconnected-(U4-RPF3{slash}USBID{slash}RF3-Pad38)") (class "Default")
      (node (ref "U4") (pin "38") (pinfunction "RPF3/USBID/RF3_38") (pintype "passive"))
    )
    (net (code "259") (name "unconnected-(U4-RPF5{slash}SCL5{slash}PMA8{slash}RF5-Pad42)") (class "Default")
      (node (ref "U4") (pin "42") (pinfunction "RPF5/SCL5/PMA8/RF5_42") (pintype "passive"))
    )
    (net (code "260") (name "unconnected-(U4-SOSCI{slash}RPC13{slash}RC13-Pad47)") (class "Default")
      (node (ref "U4") (pin "47") (pinfunction "SOSCI/RPC13/RC13_47") (pintype "passive"))
    )
    (net (code "261") (name "unconnected-(U4-TCK{slash}AN7{slash}PMA11{slash}RB12-Pad27)") (class "Default")
      (node (ref "U4") (pin "27") (pinfunction "TCK/AN7/PMA11/RB12_27") (pintype "passive"))
    )
    (net (code "262") (name "unconnected-(U4-TDI{slash}AN8{slash}RB13-Pad28)") (class "Default")
      (node (ref "U4") (pin "28") (pinfunction "TDI/AN8/RB13_28") (pintype "passive"))
    )
    (net (code "263") (name "unconnected-(U4-TDO{slash}AN6{slash}PMA12{slash}RB11-Pad24)") (class "Default")
      (node (ref "U4") (pin "24") (pinfunction "TDO/AN6/PMA12/RB11_24") (pintype "passive"))
    )
    (net (code "264") (name "unconnected-(U4-TMS{slash}CVREFOUT{slash}AN5{slash}RPB10{slash}PMA13{slash}RB10-Pad23)") (class "Default")
      (node (ref "U4") (pin "23") (pinfunction "TMS/CVREFOUT/AN5/RPB10/PMA13/RB10_23") (pintype "passive"))
    )
    (net (code "265") (name "unconnected-(U4-TRCLK{slash}SQICLK{slash}ERXD2{slash}AETXD0{slash}RPF1{slash}RF1-Pad57)") (class "Default")
      (node (ref "U4") (pin "57") (pinfunction "TRCLK/SQICLK/ERXD2/AETXD0/RPF1/RF1_57") (pintype "passive"))
    )
    (net (code "266") (name "unconnected-(U4-TRD0{slash}SQID0{slash}ERXD1{slash}PMD0{slash}RE0-Pad58)") (class "Default")
      (node (ref "U4") (pin "58") (pinfunction "TRD0/SQID0/ERXD1/PMD0/RE0_58") (pintype "passive"))
    )
    (net (code "267") (name "unconnected-(U4-TRD1{slash}SQID1{slash}ERXD0{slash}PMD1{slash}RE1-Pad61)") (class "Default")
      (node (ref "U4") (pin "61") (pinfunction "TRD1/SQID1/ERXD0/PMD1/RE1_61") (pintype "passive"))
    )
    (net (code "268") (name "unconnected-(U4-TRD2{slash}SQID2{slash}ERXDV{slash}ECRSDV{slash}AECRSDV{slash}PMD2{slash}RE2-Pad62)") (class "Default")
      (node (ref "U4") (pin "62") (pinfunction "TRD2/SQID2/ERXDV/ECRSDV/AECRSDV/PMD2/RE2_62") (pintype "passive"))
    )
    (net (code "269") (name "unconnected-(U4-TRD3{slash}SQID3{slash}ERXCLK{slash}EREFCLK{slash}RPE3{slash}PMD3{slash}RE3-Pad63)") (class "Default")
      (node (ref "U4") (pin "63") (pinfunction "TRD3/SQID3/ERXCLK/EREFCLK/RPE3/PMD3/RE3_63") (pintype "passive"))
    )
    (net (code "270") (name "unconnected-(U4-VBUS-Pad33)") (class "Default")
      (node (ref "U4") (pin "33") (pinfunction "VBUS_33") (pintype "power_in"))
    )
    (net (code "271") (name "unconnected-(U4-~{SQICS1}{slash}RPD5{slash}PMRD{slash}RD5-Pad53)") (class "Default")
      (node (ref "U4") (pin "53") (pinfunction "~{SQICS1}/RPD5/PMRD/RD5_53") (pintype "passive"))
    )
  )
)
